# Main.net
KiCad netlist of a schematic drawn in Altium Designer
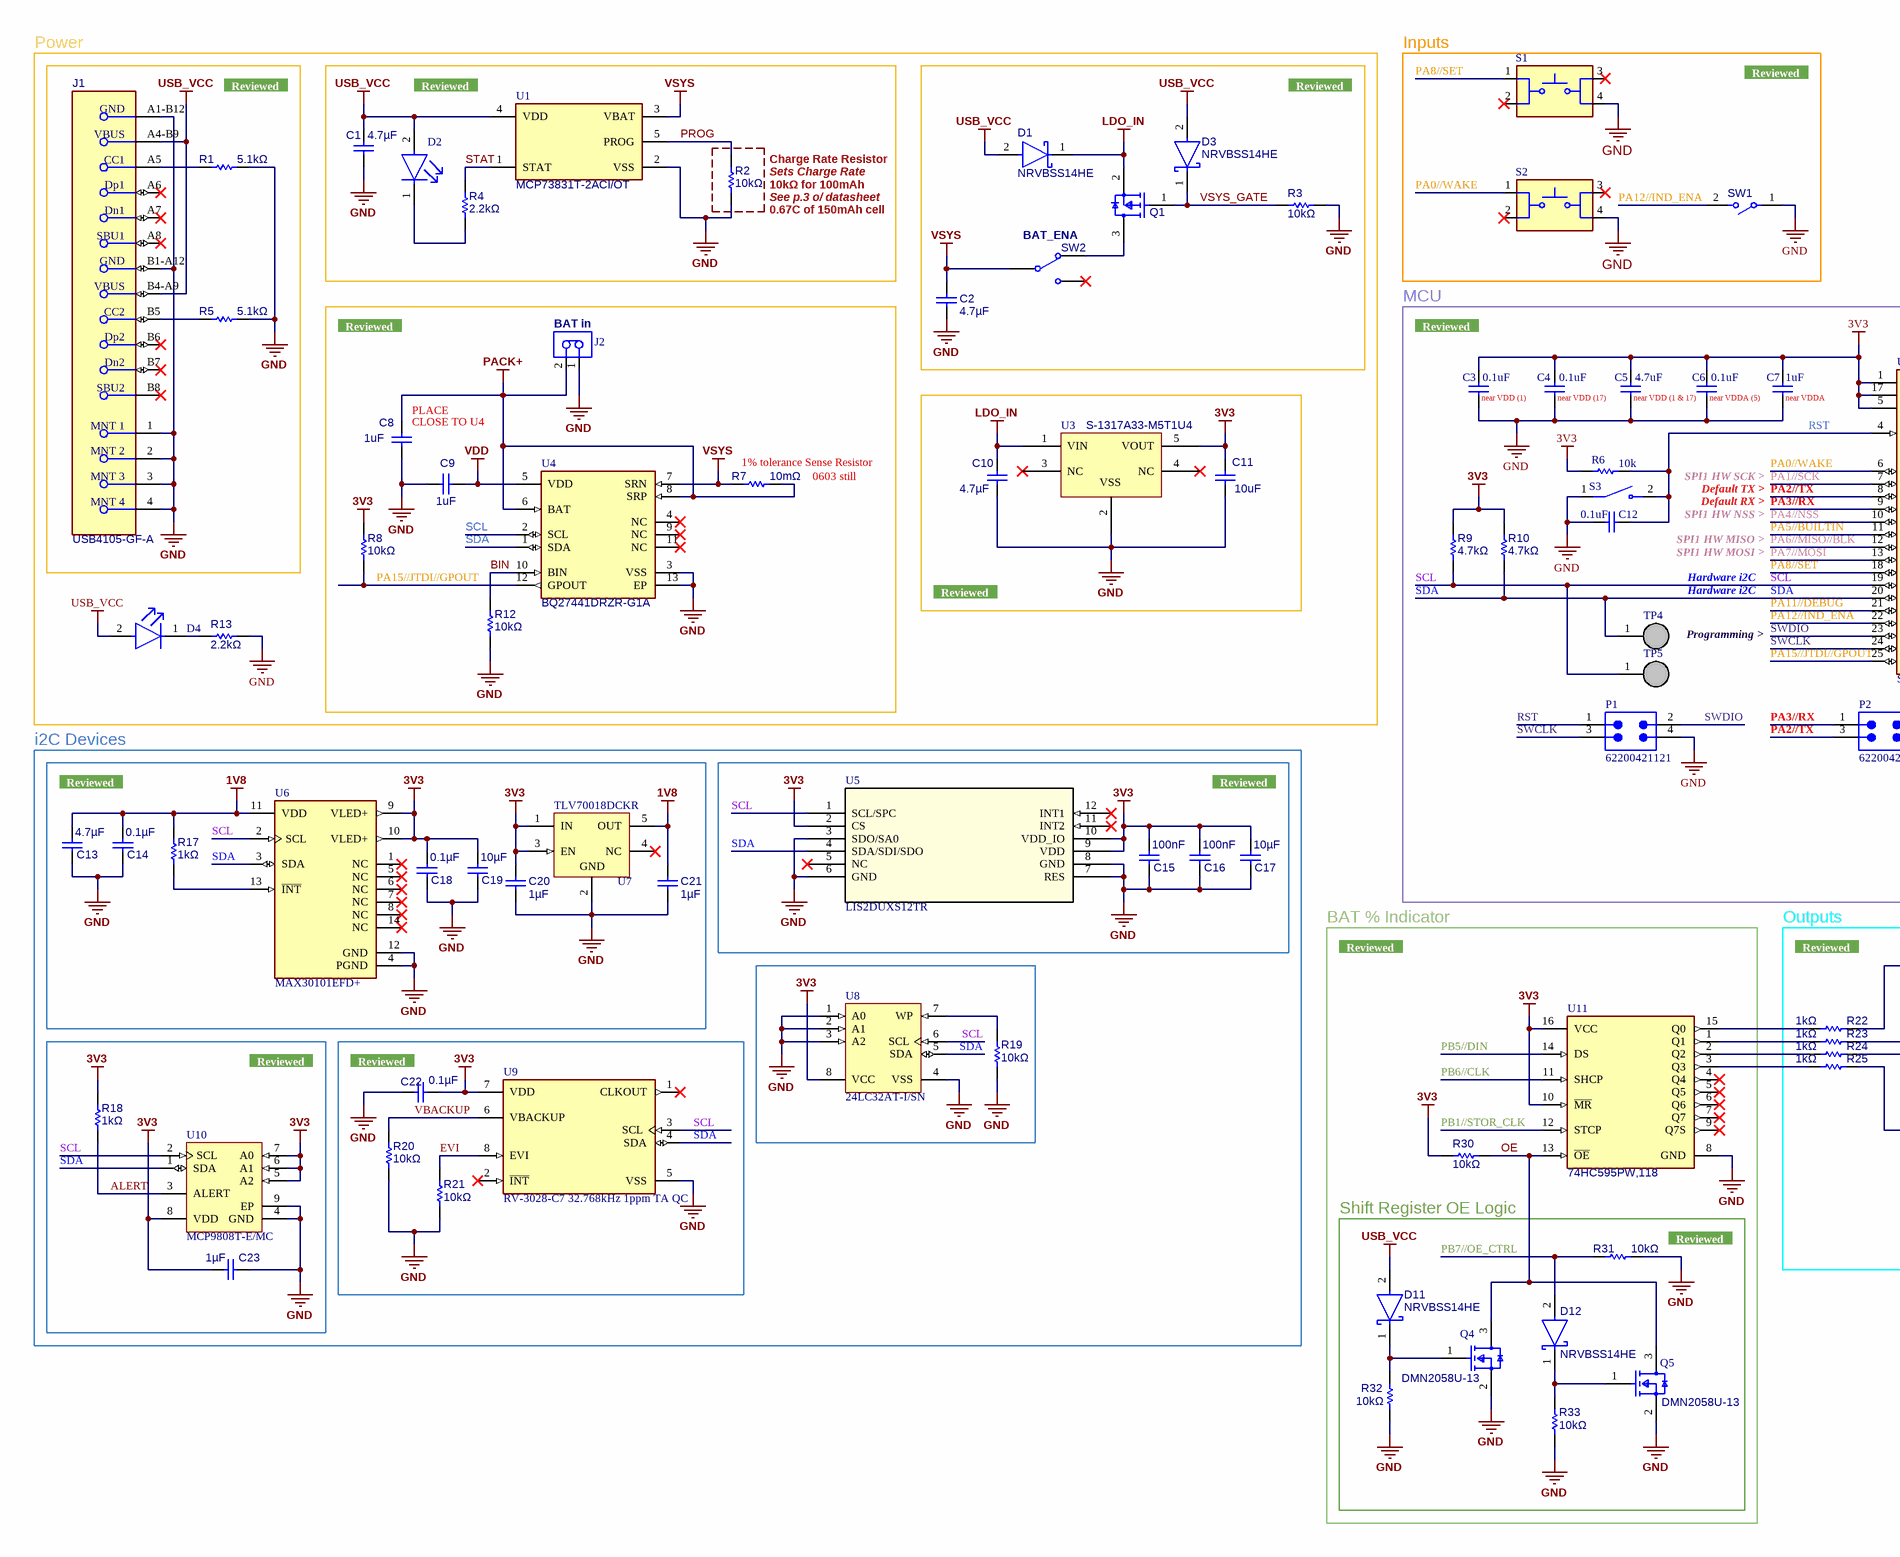
[diagram p0: Main.SchDoc, left]
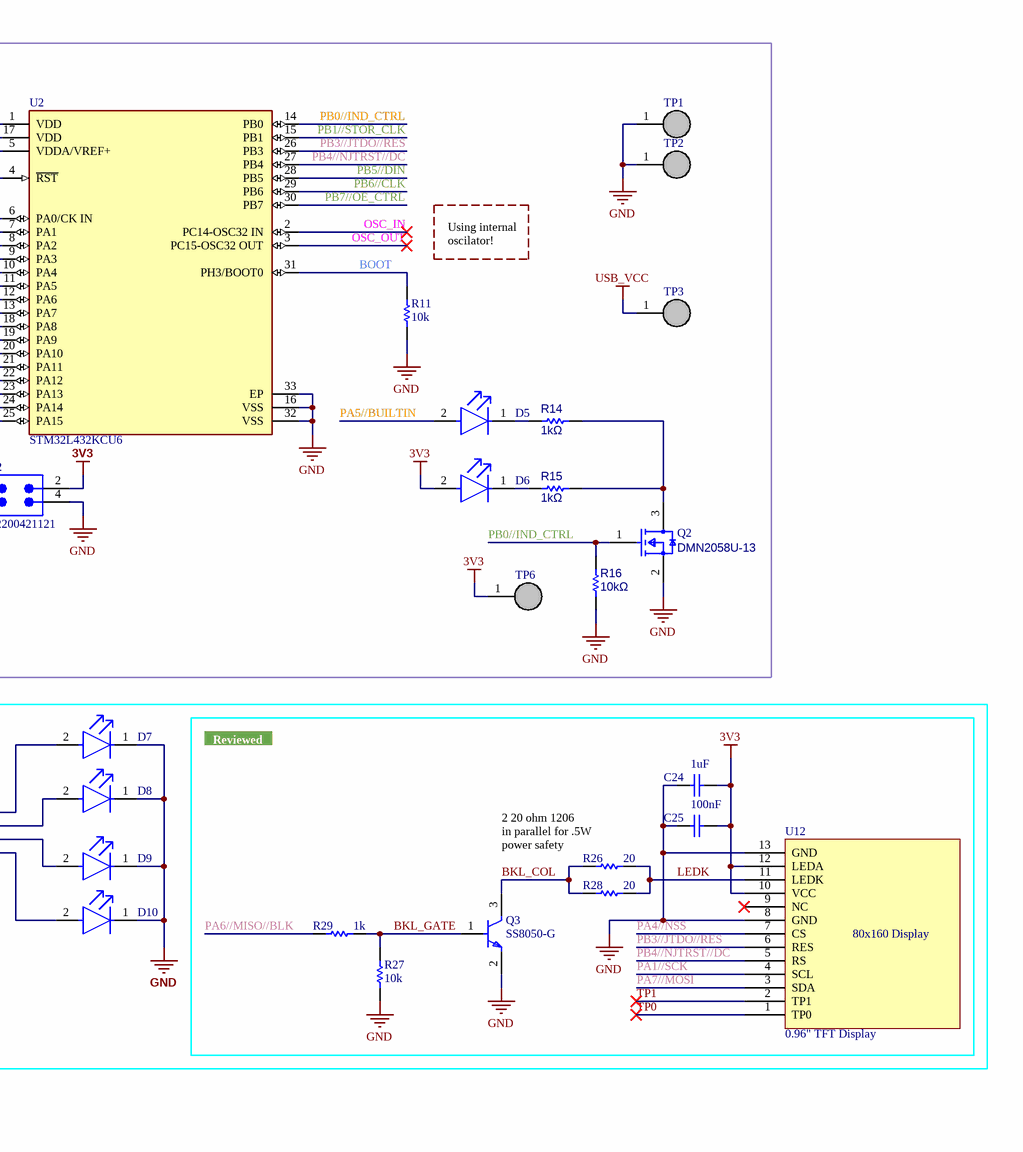
[diagram p1: Main.SchDoc, right]

(export (version "E")
  (design (tool "Eeschema 10.0.6"))
  (components
    (comp (ref "C1")
      (value "4.7µF")
      (footprint "WCAP-CSGP_0603_L1.6W0.8H0.8_Reflow")
      (libsource (lib "Altium Content Vault") (part "Capacitor_Non-Polarized"))
    )
    (comp (ref "C2")
      (value "4.7µF")
      (footprint "WCAP-CSGP_0603_L1.6W0.8H0.8_Reflow")
      (libsource (lib "Altium Content Vault") (part "Capacitor_Non-Polarized"))
    )
    (comp (ref "C3")
      (value "0.1uF")
      (footprint "CAPC1608X87X35NL15T15")
      (libsource (lib "Altium Content Vault") (part "CAP"))
    )
    (comp (ref "C4")
      (value "0.1uF")
      (footprint "CAPC1608X87X35NL15T15")
      (libsource (lib "Altium Content Vault") (part "CAP"))
    )
    (comp (ref "C5")
      (value "4.7uF")
      (footprint "CAPC1608X87X35NL15T15")
      (libsource (lib "Altium Content Vault") (part "CAP"))
    )
    (comp (ref "C6")
      (value "0.1uF")
      (footprint "CAPC1608X87X35NL15T15")
      (libsource (lib "Altium Content Vault") (part "CAP"))
    )
    (comp (ref "C7")
      (value "1uF")
      (footprint "CAPC1608X87X35NL15T15")
      (libsource (lib "Altium Content Vault") (part "CAP"))
    )
    (comp (ref "C8")
      (value "1uF")
      (footprint "WCAP-CSGP_0603_L1.6W0.8H0.8_Reflow")
      (libsource (lib "Altium Content Vault") (part "Capacitor_Non-Polarized"))
    )
    (comp (ref "C9")
      (value "1uF")
      (footprint "WCAP-CSGP_0603_L1.6W0.8H0.8_Reflow")
      (libsource (lib "Altium Content Vault") (part "Capacitor_Non-Polarized"))
    )
    (comp (ref "C10")
      (value "4.7µF")
      (footprint "WCAP-CSGP_0603_L1.6W0.8H0.8_Reflow")
      (libsource (lib "Altium Content Vault") (part "Capacitor_Non-Polarized"))
    )
    (comp (ref "C11")
      (value "10uF")
      (footprint "WCAP-CSGP_0603_L1.6W0.8H0.8_Reflow")
      (libsource (lib "Altium Content Vault") (part "Capacitor_Non-Polarized"))
    )
    (comp (ref "C12")
      (value "0.1uF")
      (footprint "CAPC1608X87X35NL15T15")
      (libsource (lib "Altium Content Vault") (part "CAP"))
    )
    (comp (ref "C13")
      (value "4.7µF")
      (footprint "WCAP-CSGP_0603_L1.6W0.8H0.8_Reflow")
      (description "10V tolerance")
      (libsource (lib "Altium Content Vault") (part "Capacitor_Non-Polarized"))
    )
    (comp (ref "C14")
      (value "0.1µF")
      (footprint "WCAP-CSGP_0603_L1.6W0.8H0.8_Reflow")
      (description "10V tolerance")
      (libsource (lib "Altium Content Vault") (part "Capacitor_Non-Polarized"))
    )
    (comp (ref "C15")
      (value "100nF")
      (footprint "WCAP-CSGP_0603_L1.6W0.8H0.8_Reflow")
      (description "10V tolerance")
      (libsource (lib "Altium Content Vault") (part "Capacitor_Non-Polarized"))
    )
    (comp (ref "C16")
      (value "100nF")
      (footprint "WCAP-CSGP_0603_L1.6W0.8H0.8_Reflow")
      (description "10V tolerance")
      (libsource (lib "Altium Content Vault") (part "Capacitor_Non-Polarized"))
    )
    (comp (ref "C17")
      (value "10µF")
      (footprint "WCAP-CSGP_0603_L1.6W0.8H0.8_Reflow")
      (description "10V tolerance")
      (libsource (lib "Altium Content Vault") (part "Capacitor_Non-Polarized"))
    )
    (comp (ref "C18")
      (value "0.1µF")
      (footprint "WCAP-CSGP_0603_L1.6W0.8H0.8_Reflow")
      (description "10V tolerance")
      (libsource (lib "Altium Content Vault") (part "Capacitor_Non-Polarized"))
    )
    (comp (ref "C19")
      (value "10µF")
      (footprint "WCAP-CSGP_0603_L1.6W0.8H0.8_Reflow")
      (description "10V tolerance")
      (libsource (lib "Altium Content Vault") (part "Capacitor_Non-Polarized"))
    )
    (comp (ref "C20")
      (value "1µF")
      (footprint "WCAP-CSGP_0603_L1.6W0.8H0.8_Reflow")
      (description "10V tolerance")
      (libsource (lib "Altium Content Vault") (part "Capacitor_Non-Polarized"))
    )
    (comp (ref "C21")
      (value "1µF")
      (footprint "WCAP-CSGP_0603_L1.6W0.8H0.8_Reflow")
      (description "10V tolerance")
      (libsource (lib "Altium Content Vault") (part "Capacitor_Non-Polarized"))
    )
    (comp (ref "C22")
      (value "0.1µF")
      (footprint "WCAP-CSGP_0603_L1.6W0.8H0.8_Reflow")
      (description "10V tolerance")
      (libsource (lib "Altium Content Vault") (part "Capacitor_Non-Polarized"))
    )
    (comp (ref "C23")
      (value "1µF")
      (footprint "WCAP-CSGP_0603_L1.6W0.8H0.8_Reflow")
      (description "10V tolerance")
      (libsource (lib "Altium Content Vault") (part "Capacitor_Non-Polarized"))
    )
    (comp (ref "C24")
      (value "1uF")
      (footprint "CAPC1608X87X35NL15T15")
      (libsource (lib "Altium Content Vault") (part "CAP"))
    )
    (comp (ref "C25")
      (value "100nF")
      (footprint "CAPC1608X87X35NL15T15")
      (libsource (lib "Altium Content Vault") (part "CAP"))
    )
    (comp (ref "D1")
      (value "NRVBSS14HE")
      (footprint "FP-477AD-MFG")
      (description "NRVBSS14HE Rectifier Diode, Schottky, 1 Phase, 1 Element, 1A, 40V V(RRM), Silicon")
      (libsource (lib "Altium Content Vault") (part "c1678fac7984e62e0809fbf79c06691"))
    )
    (comp (ref "D2")
      (value "LTST-C190KGKT")
      (footprint "FP-LTST-C190KGKT-MFG")
      (description "LED GREEN CLEAR CHIP SMD")
      (libsource (lib "Altium Content Vault") (part "8706943c75ba83719d021d2fdc84c58"))
    )
    (comp (ref "D3")
      (value "NRVBSS14HE")
      (footprint "FP-477AD-MFG")
      (description "NRVBSS14HE Rectifier Diode, Schottky, 1 Phase, 1 Element, 1A, 40V V(RRM), Silicon")
      (libsource (lib "Altium Content Vault") (part "c1678fac7984e62e0809fbf79c06691"))
    )
    (comp (ref "D4")
      (value "LTST-C190KGKT")
      (footprint "FP-LTST-C190KGKT-MFG")
      (description "LED GREEN CLEAR CHIP SMD")
      (libsource (lib "Altium Content Vault") (part "8706943c75ba83719d021d2fdc84c58"))
    )
    (comp (ref "D5")
      (value "LTST-C190KGKT")
      (footprint "FP-LTST-C190KGKT-MFG")
      (description "LED GREEN CLEAR CHIP SMD")
      (libsource (lib "Altium Content Vault") (part "8706943c75ba83719d021d2fdc84c58"))
    )
    (comp (ref "D6")
      (value "LTST-C190KGKT")
      (footprint "FP-LTST-C190KGKT-MFG")
      (description "LED GREEN CLEAR CHIP SMD")
      (libsource (lib "Altium Content Vault") (part "8706943c75ba83719d021d2fdc84c58"))
    )
    (comp (ref "D7")
      (value "LTST-C190KGKT")
      (footprint "FP-LTST-C190KGKT-MFG")
      (description "LED GREEN CLEAR CHIP SMD")
      (libsource (lib "Altium Content Vault") (part "8706943c75ba83719d021d2fdc84c58"))
    )
    (comp (ref "D8")
      (value "LTST-C190KGKT")
      (footprint "FP-LTST-C190KGKT-MFG")
      (description "LED GREEN CLEAR CHIP SMD")
      (libsource (lib "Altium Content Vault") (part "8706943c75ba83719d021d2fdc84c58"))
    )
    (comp (ref "D9")
      (value "LTST-C190KGKT")
      (footprint "FP-LTST-C190KGKT-MFG")
      (description "LED GREEN CLEAR CHIP SMD")
      (libsource (lib "Altium Content Vault") (part "8706943c75ba83719d021d2fdc84c58"))
    )
    (comp (ref "D10")
      (value "LTST-C190KGKT")
      (footprint "FP-LTST-C190KGKT-MFG")
      (description "LED GREEN CLEAR CHIP SMD")
      (libsource (lib "Altium Content Vault") (part "8706943c75ba83719d021d2fdc84c58"))
    )
    (comp (ref "D11")
      (value "NRVBSS14HE")
      (footprint "FP-477AD-MFG")
      (description "NRVBSS14HE Rectifier Diode, Schottky, 1 Phase, 1 Element, 1A, 40V V(RRM), Silicon")
      (libsource (lib "Altium Content Vault") (part "c1678fac7984e62e0809fbf79c06691"))
    )
    (comp (ref "D12")
      (value "NRVBSS14HE")
      (footprint "FP-477AD-MFG")
      (description "NRVBSS14HE Rectifier Diode, Schottky, 1 Phase, 1 Element, 1A, 40V V(RRM), Silicon")
      (libsource (lib "Altium Content Vault") (part "c1678fac7984e62e0809fbf79c06691"))
    )
    (comp (ref "J1")
      (value "USB4105-GF-A")
      (footprint "FP-USB4105-GF-A-MFG")
      (description "CONN RCPT USB2.0 TYPEC 5A")
      (fields
        (field (name "MANUFACTURER") "GCT")
        (field (name "OCTOPART") "https://octopart.com/usb4105-gf-a-gct-106627878")
      )
      (libsource (lib "Altium Content Vault") (part "e7c17a616881a82b79941196b4bec10"))
    )
    (comp (ref "J2")
      (value "B2B-PH-K-S(LF)(SN)")
      (footprint "JST-B2B-PH-K-S_V")
      (fields (field (name "MANUFACTURER") "JST"))
      (libsource (lib "Altium Content Vault") (part "CN-2P-F-QF2"))
    )
    (comp (ref "P1")
      (value "62200421121")
      (footprint "62200421121")
      (description "THT Vertical Pin Header WR-PHD, Pitch 1.27 mm, Dual Row, 4 pins")
      (libsource (lib "Altium Content Vault") (part "Header_Male_2R_04P"))
    )
    (comp (ref "P2")
      (value "62200421121")
      (footprint "62200421121")
      (description "THT Vertical Pin Header WR-PHD, Pitch 1.27 mm, Dual Row, 4 pins")
      (libsource (lib "Altium Content Vault") (part "Header_Male_2R_04P"))
    )
    (comp (ref "Q1")
      (value "IRLML6402TRPBF")
      (footprint "FP-Micro3-MFG")
      (description "MOSFET P-CH 20V 3.7A SOT-23")
      (fields
        (field (name "OCTOPART") "https://octopart.com/irlml6402trpbf-infineon-65874989")
        (field (name "MANUFACTURER") "Infineon")
      )
      (libsource (lib "Altium Content Vault") (part "566027c8dc92b5207d53ac25ab3eb60"))
    )
    (comp (ref "Q2")
      (value "DMN2058U-13")
      (footprint "FP-C04-17458-MFG")
      (description "TN2130K1-G Mosfet, N-Channel Enhancement-Mode, 300V, 25 Ohm Rohs Compliant: Yes")
      (libsource (lib "Altium Content Vault") (part "3b9c635fedb024a5347a57b145af9cc"))
    )
    (comp (ref "Q3")
      (value "SS8050-G")
      (footprint "FP-SS8050-G-MFG")
      (description "NPN TRANSISTOR 1.5A 40V SOT-23 R")
      (libsource (lib "Altium Content Vault") (part "2a1388f82443b098dcd57d24ac7632d"))
    )
    (comp (ref "Q4")
      (value "DMN2058U-13")
      (footprint "FP-C04-17458-MFG")
      (description "TN2130K1-G Mosfet, N-Channel Enhancement-Mode, 300V, 25 Ohm Rohs Compliant: Yes")
      (libsource (lib "Altium Content Vault") (part "3b9c635fedb024a5347a57b145af9cc"))
    )
    (comp (ref "Q5")
      (value "DMN2058U-13")
      (footprint "FP-C04-17458-MFG")
      (description "TN2130K1-G Mosfet, N-Channel Enhancement-Mode, 300V, 25 Ohm Rohs Compliant: Yes")
      (libsource (lib "Altium Content Vault") (part "3b9c635fedb024a5347a57b145af9cc"))
    )
    (comp (ref "R1")
      (value "5.1kΩ")
      (footprint "RESC1608X55X25NL10T15")
      (libsource (lib "Altium Content Vault") (part "RES"))
    )
    (comp (ref "R2")
      (value "10kΩ")
      (footprint "RESC1608X55X25NL10T15")
      (libsource (lib "Altium Content Vault") (part "RES"))
    )
    (comp (ref "R3")
      (value "10kΩ")
      (footprint "RESC1608X55X25NL10T15")
      (libsource (lib "Altium Content Vault") (part "RES"))
    )
    (comp (ref "R4")
      (value "2.2kΩ")
      (footprint "RESC1608X55X25NL10T15")
      (libsource (lib "Altium Content Vault") (part "RES"))
    )
    (comp (ref "R5")
      (value "5.1kΩ")
      (footprint "RESC1608X55X25NL10T15")
      (libsource (lib "Altium Content Vault") (part "RES"))
    )
    (comp (ref "R6")
      (value "10k")
      (footprint "RESC1608X55X25NL10T15")
      (fields (field (name "PART NUMBER") "RT0603BRE071KL") (field (name "MANUFACTURER") "Yageo"))
      (libsource (lib "Altium Content Vault") (part "RES"))
    )
    (comp (ref "R7")
      (value "10mΩ")
      (footprint "RESC1608X55X25NL10T15")
      (libsource (lib "Altium Content Vault") (part "RES"))
    )
    (comp (ref "R8")
      (value "10kΩ")
      (footprint "RESC1608X55X25NL10T15")
      (libsource (lib "Altium Content Vault") (part "RES"))
    )
    (comp (ref "R9")
      (value "4.7kΩ")
      (footprint "RESC1608X55X25NL10T15")
      (libsource (lib "Altium Content Vault") (part "RES"))
    )
    (comp (ref "R10")
      (value "4.7kΩ")
      (footprint "RESC1608X55X25NL10T15")
      (libsource (lib "Altium Content Vault") (part "RES"))
    )
    (comp (ref "R11")
      (value "10k")
      (footprint "RESC1608X55X25NL10T15")
      (fields (field (name "PART NUMBER") "RT0603BRE071KL") (field (name "MANUFACTURER") "Yageo"))
      (libsource (lib "Altium Content Vault") (part "RES"))
    )
    (comp (ref "R12")
      (value "10kΩ")
      (footprint "RESC1608X55X25NL10T15")
      (libsource (lib "Altium Content Vault") (part "RES"))
    )
    (comp (ref "R13")
      (value "2.2kΩ")
      (footprint "RESC1608X55X25NL10T15")
      (libsource (lib "Altium Content Vault") (part "RES"))
    )
    (comp (ref "R14")
      (value "1kΩ")
      (footprint "RESC1608X55X25NL10T15")
      (libsource (lib "Altium Content Vault") (part "RES"))
    )
    (comp (ref "R15")
      (value "1kΩ")
      (footprint "RESC1608X55X25NL10T15")
      (libsource (lib "Altium Content Vault") (part "RES"))
    )
    (comp (ref "R16")
      (value "10kΩ")
      (footprint "RESC1608X55X25NL10T15")
      (libsource (lib "Altium Content Vault") (part "RES"))
    )
    (comp (ref "R17")
      (value "1kΩ")
      (footprint "RESC1608X55X25NL10T15")
      (libsource (lib "Altium Content Vault") (part "RES"))
    )
    (comp (ref "R18")
      (value "1kΩ")
      (footprint "RESC1608X55X25NL10T15")
      (libsource (lib "Altium Content Vault") (part "RES"))
    )
    (comp (ref "R19")
      (value "10kΩ")
      (footprint "RESC1608X55X25NL10T15")
      (libsource (lib "Altium Content Vault") (part "RES"))
    )
    (comp (ref "R20")
      (value "10kΩ")
      (footprint "RESC1608X55X25NL10T15")
      (libsource (lib "Altium Content Vault") (part "RES"))
    )
    (comp (ref "R21")
      (value "10kΩ")
      (footprint "RESC1608X55X25NL10T15")
      (libsource (lib "Altium Content Vault") (part "RES"))
    )
    (comp (ref "R22")
      (value "1kΩ")
      (footprint "RESC1608X55X25NL10T15")
      (libsource (lib "Altium Content Vault") (part "RES"))
    )
    (comp (ref "R23")
      (value "1kΩ")
      (footprint "RESC1608X55X25NL10T15")
      (libsource (lib "Altium Content Vault") (part "RES"))
    )
    (comp (ref "R24")
      (value "1kΩ")
      (footprint "RESC1608X55X25NL10T15")
      (libsource (lib "Altium Content Vault") (part "RES"))
    )
    (comp (ref "R25")
      (value "1kΩ")
      (footprint "RESC1608X55X25NL10T15")
      (libsource (lib "Altium Content Vault") (part "RES"))
    )
    (comp (ref "R26")
      (value "20")
      (footprint "RESC3116X65X40NL10T20")
      (fields (field (name "MANUFACTURER") "Yageo") (field (name "PART NUMBER") "RC1206JR-0720RL"))
      (libsource (lib "Altium Content Vault") (part "RES"))
    )
    (comp (ref "R27")
      (value "10k")
      (footprint "RESC1608X55X25NL10T15")
      (fields (field (name "PART NUMBER") "RT0603BRE071KL") (field (name "MANUFACTURER") "Yageo"))
      (libsource (lib "Altium Content Vault") (part "RES"))
    )
    (comp (ref "R28")
      (value "20")
      (footprint "RESC3116X65X40NL10T20")
      (fields (field (name "MANUFACTURER") "Yageo") (field (name "PART NUMBER") "RC1206JR-0720RL"))
      (libsource (lib "Altium Content Vault") (part "RES"))
    )
    (comp (ref "R29")
      (value "1k")
      (footprint "RESC1608X55X25NL10T15")
      (fields (field (name "PART NUMBER") "RT0603BRE071KL") (field (name "MANUFACTURER") "Yageo"))
      (libsource (lib "Altium Content Vault") (part "RES"))
    )
    (comp (ref "R30")
      (value "10kΩ")
      (footprint "RESC1608X55X25NL10T15")
      (libsource (lib "Altium Content Vault") (part "RES"))
    )
    (comp (ref "R31")
      (value "10kΩ")
      (footprint "RESC1608X55X25NL10T15")
      (libsource (lib "Altium Content Vault") (part "RES"))
    )
    (comp (ref "R32")
      (value "10kΩ")
      (footprint "RESC1608X55X25NL10T15")
      (libsource (lib "Altium Content Vault") (part "RES"))
    )
    (comp (ref "R33")
      (value "10kΩ")
      (footprint "RESC1608X55X25NL10T15")
      (libsource (lib "Altium Content Vault") (part "RES"))
    )
    (comp (ref "S1")
      (value "SWT0325-073016TSK_REVA")
      (footprint "SW_SWT0325-073016TSK_REVA")
      (description "6mm x 6mm Through Hole Tactile Switch")
      (fields (field (name "MF") "Global Connector Technology") (field (name "MP") "SWT0325-073016TSK"))
      (libsource (lib "SWT0325-073016TSK_REVA") (part "SWT0325-073016TSK_REVA"))
    )
    (comp (ref "S2")
      (value "SWT0325-073016TSK_REVA")
      (footprint "SW_SWT0325-073016TSK_REVA")
      (description "6mm x 6mm Through Hole Tactile Switch")
      (fields (field (name "MF") "Global Connector Technology") (field (name "MP") "SWT0325-073016TSK"))
      (libsource (lib "SWT0325-073016TSK_REVA") (part "SWT0325-073016TSK_REVA"))
    )
    (comp (ref "S3")
      (value "TS09-63-25-WT-260-SMT-TR")
      (footprint "SW_TS09-63-25-WT-260-SMT-TR")
      (description "6.1 x 3.7 mm, 2.5 mm Actuator Height, 260 gf, White, Surface Mount, SPST, Tactile Switch")
      (fields (field (name "MF") "Same Sky"))
      (libsource (lib "TS09-63-25-WT-260-SMT-TR") (part "TS09-63-25-WT-260-SMT-TR"))
    )
    (comp (ref "SW1")
      (value "B3U-1000P-B")
      (footprint "FP-B3U-1000P-B-MFG")
      (description "SWITCH TACTILE SPST-NO 0.05A 12V")
      (fields
        (field (name "OCTOPART") "https://octopart.com/b3u-1000p-b-omron-1057356")
        (field (name "MANUFACTURER") "Omron")
      )
      (libsource (lib "Altium Content Vault") (part "bb27bde45df87f1f469753f287ef5ae"))
    )
    (comp (ref "SW2")
      (value "450404015514")
      (footprint "450404015514")
      (description "450404015514 Slide Switch, 0.3A, 5Vdc, Smd Rohs Compliant: Yes")
      (libsource (lib "Altium Content Vault") (part "SPDT"))
    )
    (comp (ref "TP1")
      (value "Testpoint")
      (footprint "Testpoint Footprint")
      (libsource (lib "DebuggingLib") (part "Testpoint"))
    )
    (comp (ref "TP2")
      (value "Testpoint")
      (footprint "Testpoint Footprint")
      (libsource (lib "DebuggingLib") (part "Testpoint"))
    )
    (comp (ref "TP3")
      (value "Testpoint")
      (footprint "Testpoint Footprint")
      (libsource (lib "DebuggingLib") (part "Testpoint"))
    )
    (comp (ref "TP4")
      (value "Testpoint")
      (footprint "Testpoint Footprint")
      (libsource (lib "DebuggingLib") (part "Testpoint"))
    )
    (comp (ref "TP5")
      (value "Testpoint")
      (footprint "Testpoint Footprint")
      (libsource (lib "DebuggingLib") (part "Testpoint"))
    )
    (comp (ref "TP6")
      (value "Testpoint")
      (footprint "Testpoint Footprint")
      (libsource (lib "DebuggingLib") (part "Testpoint"))
    )
    (comp (ref "U1")
      (value "MCP73831T-2ACI/OT")
      (footprint "FP-C04-091-OT-MFG")
      (description "IC CONTROLLR LI-ION 4.2V SOT23-5")
      (libsource (lib "Altium Content Vault") (part "61f5a3bb3429d9e0caadea342aa3b19"))
    )
    (comp (ref "U2")
      (value "STM32L432KCU6")
      (footprint "FP-UFQFPN32-A0B8-MFG")
      (description "IC MCU 32BIT 256KB FLASH 32QFPN")
      (fields
        (field (name "OCTOPART") "https://octopart.com/stm32l432kcu6-stmicroelectronics-71093510")
        (field (name "MANUFACTURER") "STMicroelectronics")
      )
      (libsource (lib "Altium Content Vault") (part "f3240dca552e0aa49c1b4baba198c12"))
    )
    (comp (ref "U3")
      (value "S-1317A33-M5T1U4")
      (footprint "S-1317A33-M5T1U4")
      (libsource (lib "1317A33-M5T1U4") (part "S-1317A33-M5T1U4"))
    )
    (comp (ref "U4")
      (value "BQ27441DRZR-G1A")
      (footprint "FP-DRZ0012A-MFG")
      (description "IC BATT FUEL GAUGE LI-ION 12SON")
      (fields
        (field (name "OCTOPART") "https://octopart.com/bq27441drzr-g1a-texas+instruments-30555829")
        (field (name "MANUFACTURER") "Texas Instruments")
      )
      (libsource (lib "Altium Content Vault") (part "0f562f18464a1f07b55dcd927f1fdf2"))
    )
    (comp (ref "U5")
      (value "LIS2DUXS12TR")
      (footprint "QFN_DUXS12_STM")
      (fields (field (name "COPYRIGHT") "Copyright (C) 2025 Ultra Librarian. All rights reserved."))
      (libsource (lib "LIS2DUXS12TR") (part "LIS2DUXS12TR"))
    )
    (comp (ref "U6")
      (value "MAX30101EFD+")
      (footprint "FP-F143A5-1-MFG")
      (description "INTEGRATED OPTICAL SENSOR")
      (fields
        (field (name "MANUFACTURER") "Maxim Integrated")
        (field (name "OCTOPART") "https://octopart.com/max30101efd%2B-maxim+integrated-57054333")
      )
      (libsource (lib "Altium Content Vault") (part "7412f82398c18c21c59cad441ae59a4"))
    )
    (comp (ref "U7")
      (value "TLV70018DCKR")
      (footprint "DCK0005A_L")
      (fields (field (name "MANUFACTURER") "Texas Instruments"))
      (libsource (lib "Altium Content Vault") (part "TI-TXX7XXXX-5"))
    )
    (comp (ref "U8")
      (value "24LC32AT-I/SN")
      (footprint "SOIC-SN8_L")
      (description "32Kbit, 400kHz, 2.5V, I2C Serial EEPROM, 8-Pin SOIC 150mil, Industrial Temperature, Tape and Reel")
      (libsource (lib "Altium Content Vault") (part "MEM-SEEPROM-34AA02-IL8"))
    )
    (comp (ref "U9")
      (value "RV-3028-C7 32.768kHz 1ppm TA QC")
      (footprint "FP-RV-3028-C7_32_768kHz_1-MFG")
      (description "Real Time Clock Serial 2byte Clock/Calendar/Alarm/Timer/Battery Backup 8-Pin CSMD T/R")
      (fields
        (field (name "OCTOPART") "https://octopart.com/rv-3028-c7+32.768khz+1ppm+ta+qc-micro+crystal-98880451")
        (field (name "MANUFACTURER") "Micro Crystal")
      )
      (libsource (lib "Altium Content Vault") (part "f06799675b941e5ee1fb77ef065374c"))
    )
    (comp (ref "U10")
      (value "MCP9808T-E/MC")
      (footprint "MCHP-DFN-MC8_V")
      (fields (field (name "MANUFACTURER") "Microchip"))
      (libsource (lib "Altium Content Vault") (part "MCHP-MCP9808-DFN-8"))
    )
    (comp (ref "U11")
      (value "74HC595PW,118")
      (footprint "FP-SOT403-1-MFG")
      (description "IC SHIFT REGISTER 8BIT 16TSSOP")
      (libsource (lib "Altium Content Vault") (part "27683e23285b137cd268a0f18c66bed"))
    )
    (comp (ref "U12")
      (value "0.96\" TFT Display")
      (footprint "PCBComponent_1")
      (libsource (lib "disp_0.96") (part "0.96{dblquote} TFT Display"))
    )
  )
  (nets
    (net (code "1") (name "/ALERT") (class "Default")
      (node (ref "R18") (pin "1") (pinfunction "1_1") (pintype "passive"))
      (node (ref "U10") (pin "3") (pinfunction "ALERT_3") (pintype "open_collector"))
    )
    (net (code "2") (name "/BIN") (class "Default")
      (node (ref "R12") (pin "2") (pinfunction "2_2") (pintype "passive"))
      (node (ref "U4") (pin "10") (pinfunction "BIN_10") (pintype "input"))
    )
    (net (code "3") (name "/BKL_COL") (class "Default")
      (node (ref "Q3") (pin "3") (pinfunction "C_3") (pintype "passive"))
      (node (ref "R26") (pin "1") (pinfunction "1_1") (pintype "passive"))
      (node (ref "R28") (pin "1") (pinfunction "1_1") (pintype "passive"))
    )
    (net (code "4") (name "/BKL_GATE") (class "Default")
      (node (ref "Q3") (pin "1") (pinfunction "B_1") (pintype "passive"))
      (node (ref "R27") (pin "2") (pinfunction "2_2") (pintype "passive"))
      (node (ref "R29") (pin "2") (pinfunction "2_2") (pintype "passive"))
    )
    (net (code "5") (name "/BOOT") (class "Default")
      (node (ref "R11") (pin "2") (pinfunction "2_2") (pintype "passive"))
      (node (ref "U2") (pin "31") (pinfunction "PH3/BOOT0_31") (pintype "bidirectional"))
    )
    (net (code "6") (name "/EVI") (class "Default")
      (node (ref "R21") (pin "2") (pinfunction "2_2") (pintype "passive"))
      (node (ref "U9") (pin "8") (pinfunction "EVI_8") (pintype "input"))
    )
    (net (code "7") (name "/LEDK") (class "Default")
      (node (ref "R26") (pin "2") (pinfunction "2_2") (pintype "passive"))
      (node (ref "R28") (pin "2") (pinfunction "2_2") (pintype "passive"))
      (node (ref "U12") (pin "11") (pinfunction "LEDK_11") (pintype "passive"))
    )
    (net (code "8") (name "/OE") (class "Default")
      (node (ref "Q4") (pin "3") (pinfunction "D_3") (pintype "passive"))
      (node (ref "Q5") (pin "3") (pinfunction "D_3") (pintype "passive"))
      (node (ref "R30") (pin "2") (pinfunction "2_2") (pintype "passive"))
      (node (ref "U11") (pin "13") (pinfunction "~{OE}_13") (pintype "input"))
    )
    (net (code "9") (name "/OSC_IN") (class "Default")
      (node (ref "U2") (pin "2") (pinfunction "PC14-OSC32_IN_2") (pintype "bidirectional+no_connect"))
    )
    (net (code "10") (name "/OSC_OUT") (class "Default")
      (node (ref "U2") (pin "3") (pinfunction "PC15-OSC32_OUT_3") (pintype "bidirectional+no_connect"))
    )
    (net (code "11") (name "/PA0{slash}{slash}WAKE") (class "Default")
      (node (ref "S2") (pin "1") (pinfunction "1_1") (pintype "passive"))
      (node (ref "U2") (pin "6") (pinfunction "PA0/CK_IN_6") (pintype "bidirectional"))
    )
    (net (code "12") (name "/PA1{slash}{slash}SCK") (class "Default")
      (node (ref "U12") (pin "4") (pinfunction "SCL_4") (pintype "passive"))
      (node (ref "U2") (pin "7") (pinfunction "PA1_7") (pintype "bidirectional"))
    )
    (net (code "13") (name "/PA2{slash}{slash}TX") (class "Default")
      (node (ref "P2") (pin "3") (pinfunction "3_3") (pintype "passive"))
      (node (ref "U2") (pin "8") (pinfunction "PA2_8") (pintype "bidirectional"))
    )
    (net (code "14") (name "/PA3{slash}{slash}RX") (class "Default")
      (node (ref "P2") (pin "1") (pinfunction "1_1") (pintype "passive"))
      (node (ref "U2") (pin "9") (pinfunction "PA3_9") (pintype "bidirectional"))
    )
    (net (code "15") (name "/PA4{slash}{slash}NSS") (class "Default")
      (node (ref "U12") (pin "7") (pinfunction "CS_7") (pintype "passive"))
      (node (ref "U2") (pin "10") (pinfunction "PA4_10") (pintype "bidirectional"))
    )
    (net (code "16") (name "/PA5{slash}{slash}BUILTIN") (class "Default")
      (node (ref "D5") (pin "2") (pinfunction "A_2") (pintype "passive"))
      (node (ref "U2") (pin "11") (pinfunction "PA5_11") (pintype "bidirectional"))
    )
    (net (code "17") (name "/PA6{slash}{slash}MISO{slash}{slash}BLK") (class "Default")
      (node (ref "R29") (pin "1") (pinfunction "1_1") (pintype "passive"))
      (node (ref "U2") (pin "12") (pinfunction "PA6_12") (pintype "bidirectional"))
    )
    (net (code "18") (name "/PA7{slash}{slash}MOSI") (class "Default")
      (node (ref "U12") (pin "3") (pinfunction "SDA_3") (pintype "passive"))
      (node (ref "U2") (pin "13") (pinfunction "PA7_13") (pintype "bidirectional"))
    )
    (net (code "19") (name "/PA8{slash}{slash}SET") (class "Default")
      (node (ref "S1") (pin "1") (pinfunction "1_1") (pintype "passive"))
      (node (ref "U2") (pin "18") (pinfunction "PA8_18") (pintype "bidirectional"))
    )
    (net (code "20") (name "/PA11{slash}{slash}DEBUG") (class "Default")
      (node (ref "U2") (pin "21") (pinfunction "PA11_21") (pintype "bidirectional"))
    )
    (net (code "21") (name "/PA12{slash}{slash}IND_ENA") (class "Default")
      (node (ref "SW1") (pin "2") (pinfunction "2_2") (pintype "passive"))
      (node (ref "U2") (pin "22") (pinfunction "PA12_22") (pintype "bidirectional"))
    )
    (net (code "22") (name "/PA15{slash}{slash}JTDI{slash}{slash}GPOUT") (class "Default")
      (node (ref "R8") (pin "1") (pinfunction "1_1") (pintype "passive"))
      (node (ref "U2") (pin "25") (pinfunction "PA15_25") (pintype "bidirectional"))
      (node (ref "U4") (pin "12") (pinfunction "GPOUT_12") (pintype "output"))
    )
    (net (code "23") (name "/PB0{slash}{slash}IND_CTRL") (class "Default")
      (node (ref "Q2") (pin "1") (pinfunction "G_1") (pintype "passive"))
      (node (ref "R16") (pin "2") (pinfunction "2_2") (pintype "passive"))
      (node (ref "U2") (pin "14") (pinfunction "PB0_14") (pintype "bidirectional"))
    )
    (net (code "24") (name "/PB1{slash}{slash}STOR_CLK") (class "Default")
      (node (ref "U11") (pin "12") (pinfunction "STCP_12") (pintype "input"))
      (node (ref "U2") (pin "15") (pinfunction "PB1_15") (pintype "bidirectional"))
    )
    (net (code "25") (name "/PB3{slash}{slash}JTDO{slash}{slash}RES") (class "Default")
      (node (ref "U12") (pin "6") (pinfunction "RES_6") (pintype "passive"))
      (node (ref "U2") (pin "26") (pinfunction "PB3_26") (pintype "bidirectional"))
    )
    (net (code "26") (name "/PB4{slash}{slash}NJTRST{slash}{slash}DC") (class "Default")
      (node (ref "U12") (pin "5") (pinfunction "RS_5") (pintype "passive"))
      (node (ref "U2") (pin "27") (pinfunction "PB4_27") (pintype "bidirectional"))
    )
    (net (code "27") (name "/PB5{slash}{slash}DIN") (class "Default")
      (node (ref "U11") (pin "14") (pinfunction "DS_14") (pintype "input"))
      (node (ref "U2") (pin "28") (pinfunction "PB5_28") (pintype "bidirectional"))
    )
    (net (code "28") (name "/PB6{slash}{slash}CLK") (class "Default")
      (node (ref "U11") (pin "11") (pinfunction "SHCP_11") (pintype "input"))
      (node (ref "U2") (pin "29") (pinfunction "PB6_29") (pintype "bidirectional"))
    )
    (net (code "29") (name "/PB7{slash}{slash}OE_CTRL") (class "Default")
      (node (ref "D12") (pin "2") (pinfunction "A_2") (pintype "passive"))
      (node (ref "R31") (pin "1") (pinfunction "1_1") (pintype "passive"))
      (node (ref "U2") (pin "30") (pinfunction "PB7_30") (pintype "bidirectional"))
    )
    (net (code "30") (name "/PROG") (class "Default")
      (node (ref "R2") (pin "1") (pinfunction "1_1") (pintype "passive"))
      (node (ref "U1") (pin "5") (pinfunction "PROG_5") (pintype "passive"))
    )
    (net (code "31") (name "/RST") (class "Default")
      (node (ref "C12") (pin "2") (pinfunction "2_2") (pintype "passive"))
      (node (ref "P1") (pin "1") (pinfunction "1_1") (pintype "passive"))
      (node (ref "R6") (pin "1") (pinfunction "1_1") (pintype "passive"))
      (node (ref "S3") (pin "2") (pinfunction "2_2") (pintype "passive"))
      (node (ref "U2") (pin "4") (pinfunction "~{RST}_4") (pintype "input"))
    )
    (net (code "32") (name "/SCL") (class "Default")
      (node (ref "R9") (pin "2") (pinfunction "2_2") (pintype "passive"))
      (node (ref "TP5") (pin "1") (pintype "passive"))
      (node (ref "U10") (pin "2") (pinfunction "SCL_2") (pintype "input"))
      (node (ref "U2") (pin "19") (pinfunction "PA9_19") (pintype "bidirectional"))
      (node (ref "U4") (pin "2") (pinfunction "SCL_2") (pintype "bidirectional"))
      (node (ref "U5") (pin "1") (pinfunction "SCL/SPC_1") (pintype "passive"))
      (node (ref "U6") (pin "2") (pinfunction "SCL_2") (pintype "input"))
      (node (ref "U8") (pin "6") (pinfunction "SCL_6") (pintype "input"))
      (node (ref "U9") (pin "3") (pinfunction "SCL_3") (pintype "input"))
    )
    (net (code "33") (name "/SDA") (class "Default")
      (node (ref "R10") (pin "2") (pinfunction "2_2") (pintype "passive"))
      (node (ref "TP4") (pin "1") (pintype "passive"))
      (node (ref "U10") (pin "1") (pinfunction "SDA_1") (pintype "bidirectional"))
      (node (ref "U2") (pin "20") (pinfunction "PA10_20") (pintype "bidirectional"))
      (node (ref "U4") (pin "1") (pinfunction "SDA_1") (pintype "bidirectional"))
      (node (ref "U5") (pin "4") (pinfunction "SDA/SDI/SDO_4") (pintype "passive"))
      (node (ref "U6") (pin "3") (pinfunction "SDA_3") (pintype "bidirectional"))
      (node (ref "U8") (pin "5") (pinfunction "SDA_5") (pintype "bidirectional"))
      (node (ref "U9") (pin "4") (pinfunction "SDA_4") (pintype "bidirectional"))
    )
    (net (code "34") (name "/STAT") (class "Default")
      (node (ref "R4") (pin "2") (pinfunction "2_2") (pintype "passive"))
      (node (ref "U1") (pin "1") (pinfunction "STAT_1") (pintype "passive"))
    )
    (net (code "35") (name "/SWCLK") (class "Default")
      (node (ref "P1") (pin "3") (pinfunction "3_3") (pintype "passive"))
      (node (ref "U2") (pin "24") (pinfunction "PA14_24") (pintype "bidirectional"))
    )
    (net (code "36") (name "/SWDIO") (class "Default")
      (node (ref "P1") (pin "2") (pinfunction "2_2") (pintype "passive"))
      (node (ref "U2") (pin "23") (pinfunction "PA13_23") (pintype "bidirectional"))
    )
    (net (code "37") (name "/TP0") (class "Default")
      (node (ref "U12") (pin "1") (pinfunction "TP0_1") (pintype "passive+no_connect"))
    )
    (net (code "38") (name "/TP1") (class "Default")
      (node (ref "U12") (pin "2") (pinfunction "TP1_2") (pintype "passive+no_connect"))
    )
    (net (code "39") (name "/VBACKUP") (class "Default")
      (node (ref "R20") (pin "2") (pinfunction "2_2") (pintype "passive"))
      (node (ref "U9") (pin "6") (pinfunction "VBACKUP_6") (pintype "power_in"))
    )
    (net (code "40") (name "/VSYS_GATE") (class "Default")
      (node (ref "D3") (pin "1") (pinfunction "C_1") (pintype "passive"))
      (node (ref "Q1") (pin "1") (pinfunction "G_1") (pintype "passive"))
      (node (ref "R3") (pin "1") (pinfunction "1_1") (pintype "passive"))
    )
    (net (code "41") (name "1V8") (class "Default")
      (node (ref "C13") (pin "1") (pinfunction "1_1") (pintype "passive"))
      (node (ref "C14") (pin "1") (pinfunction "1_1") (pintype "passive"))
      (node (ref "C21") (pin "2") (pinfunction "2_2") (pintype "passive"))
      (node (ref "R17") (pin "2") (pinfunction "2_2") (pintype "passive"))
      (node (ref "U6") (pin "11") (pinfunction "VDD_11") (pintype "power_in"))
      (node (ref "U7") (pin "5") (pinfunction "OUT_5") (pintype "power_in"))
    )
    (net (code "42") (name "3V3") (class "Default")
      (node (ref "C11") (pin "2") (pinfunction "2_2") (pintype "passive"))
      (node (ref "C15") (pin "1") (pinfunction "1_1") (pintype "passive"))
      (node (ref "C16") (pin "1") (pinfunction "1_1") (pintype "passive"))
      (node (ref "C17") (pin "1") (pinfunction "1_1") (pintype "passive"))
      (node (ref "C18") (pin "1") (pinfunction "1_1") (pintype "passive"))
      (node (ref "C19") (pin "1") (pinfunction "1_1") (pintype "passive"))
      (node (ref "C20") (pin "2") (pinfunction "2_2") (pintype "passive"))
      (node (ref "C22") (pin "1") (pinfunction "1_1") (pintype "passive"))
      (node (ref "C23") (pin "1") (pinfunction "1_1") (pintype "passive"))
      (node (ref "C24") (pin "1") (pinfunction "1_1") (pintype "passive"))
      (node (ref "C25") (pin "1") (pinfunction "1_1") (pintype "passive"))
      (node (ref "C3") (pin "1") (pinfunction "1_1") (pintype "passive"))
      (node (ref "C4") (pin "1") (pinfunction "1_1") (pintype "passive"))
      (node (ref "C5") (pin "1") (pinfunction "1_1") (pintype "passive"))
      (node (ref "C6") (pin "1") (pinfunction "1_1") (pintype "passive"))
      (node (ref "C7") (pin "1") (pinfunction "1_1") (pintype "passive"))
      (node (ref "D6") (pin "2") (pinfunction "A_2") (pintype "passive"))
      (node (ref "P2") (pin "2") (pinfunction "2_2") (pintype "passive"))
      (node (ref "R10") (pin "1") (pinfunction "1_1") (pintype "passive"))
      (node (ref "R18") (pin "2") (pinfunction "2_2") (pintype "passive"))
      (node (ref "R30") (pin "1") (pinfunction "1_1") (pintype "passive"))
      (node (ref "R6") (pin "2") (pinfunction "2_2") (pintype "passive"))
      (node (ref "R8") (pin "2") (pinfunction "2_2") (pintype "passive"))
      (node (ref "R9") (pin "1") (pinfunction "1_1") (pintype "passive"))
      (node (ref "TP6") (pin "1") (pintype "passive"))
      (node (ref "U10") (pin "5") (pinfunction "A2_5") (pintype "input"))
      (node (ref "U10") (pin "6") (pinfunction "A1_6") (pintype "input"))
      (node (ref "U10") (pin "7") (pinfunction "A0_7") (pintype "input"))
      (node (ref "U10") (pin "8") (pinfunction "VDD_8") (pintype "power_in"))
      (node (ref "U11") (pin "10") (pinfunction "~{MR}_10") (pintype "input"))
      (node (ref "U11") (pin "16") (pinfunction "VCC_16") (pintype "power_in"))
      (node (ref "U12") (pin "10") (pinfunction "VCC_10") (pintype "passive"))
      (node (ref "U12") (pin "12") (pinfunction "LEDA_12") (pintype "passive"))
      (node (ref "U2") (pin "1") (pinfunction "VDD_1") (pintype "power_in"))
      (node (ref "U2") (pin "17") (pinfunction "VDD_17") (pintype "power_in"))
      (node (ref "U2") (pin "5") (pinfunction "VDDA/VREF+_5") (pintype "power_in"))
      (node (ref "U3") (pin "5") (pinfunction "VOUT_5") (pintype "passive"))
      (node (ref "U5") (pin "10") (pinfunction "VDD_IO_10") (pintype "power_in"))
      (node (ref "U5") (pin "2") (pinfunction "CS_2") (pintype "passive"))
      (node (ref "U5") (pin "9") (pinfunction "VDD_9") (pintype "power_in"))
      (node (ref "U6") (pin "10") (pinfunction "VLED+_10") (pintype "output"))
      (node (ref "U6") (pin "9") (pinfunction "VLED+_9") (pintype "output"))
      (node (ref "U7") (pin "1") (pinfunction "IN_1") (pintype "power_in"))
      (node (ref "U7") (pin "3") (pinfunction "EN_3") (pintype "input"))
      (node (ref "U8") (pin "8") (pinfunction "VCC_8") (pintype "power_in"))
      (node (ref "U9") (pin "7") (pinfunction "VDD_7") (pintype "power_in"))
    )
    (net (code "43") (name "GND") (class "Default")
      (node (ref "C1") (pin "1") (pinfunction "1_1") (pintype "passive"))
      (node (ref "C10") (pin "1") (pinfunction "1_1") (pintype "passive"))
      (node (ref "C11") (pin "1") (pinfunction "1_1") (pintype "passive"))
      (node (ref "C12") (pin "1") (pinfunction "1_1") (pintype "passive"))
      (node (ref "C13") (pin "2") (pinfunction "2_2") (pintype "passive"))
      (node (ref "C14") (pin "2") (pinfunction "2_2") (pintype "passive"))
      (node (ref "C15") (pin "2") (pinfunction "2_2") (pintype "passive"))
      (node (ref "C16") (pin "2") (pinfunction "2_2") (pintype "passive"))
      (node (ref "C17") (pin "2") (pinfunction "2_2") (pintype "passive"))
      (node (ref "C18") (pin "2") (pinfunction "2_2") (pintype "passive"))
      (node (ref "C19") (pin "2") (pinfunction "2_2") (pintype "passive"))
      (node (ref "C2") (pin "1") (pinfunction "1_1") (pintype "passive"))
      (node (ref "C20") (pin "1") (pinfunction "1_1") (pintype "passive"))
      (node (ref "C21") (pin "1") (pinfunction "1_1") (pintype "passive"))
      (node (ref "C22") (pin "2") (pinfunction "2_2") (pintype "passive"))
      (node (ref "C23") (pin "2") (pinfunction "2_2") (pintype "passive"))
      (node (ref "C24") (pin "2") (pinfunction "2_2") (pintype "passive"))
      (node (ref "C25") (pin "2") (pinfunction "2_2") (pintype "passive"))
      (node (ref "C3") (pin "2") (pinfunction "2_2") (pintype "passive"))
      (node (ref "C4") (pin "2") (pinfunction "2_2") (pintype "passive"))
      (node (ref "C5") (pin "2") (pinfunction "2_2") (pintype "passive"))
      (node (ref "C6") (pin "2") (pinfunction "2_2") (pintype "passive"))
      (node (ref "C7") (pin "2") (pinfunction "2_2") (pintype "passive"))
      (node (ref "C8") (pin "2") (pinfunction "2_2") (pintype "passive"))
      (node (ref "C9") (pin "2") (pinfunction "2_2") (pintype "passive"))
      (node (ref "D10") (pin "1") (pinfunction "C_1") (pintype "passive"))
      (node (ref "D7") (pin "1") (pinfunction "C_1") (pintype "passive"))
      (node (ref "D8") (pin "1") (pinfunction "C_1") (pintype "passive"))
      (node (ref "D9") (pin "1") (pinfunction "C_1") (pintype "passive"))
      (node (ref "J1") (pin "1") (pinfunction "MNT_1_1") (pintype "power_in"))
      (node (ref "J1") (pin "2") (pinfunction "MNT_2_2") (pintype "power_in"))
      (node (ref "J1") (pin "3") (pinfunction "MNT_3_3") (pintype "power_in"))
      (node (ref "J1") (pin "4") (pinfunction "MNT_4_4") (pintype "power_in"))
      (node (ref "J1") (pin "A1-B12") (pinfunction "GND_A1-B12") (pintype "power_in"))
      (node (ref "J1") (pin "B1-A12") (pinfunction "GND_B1-A12") (pintype "bidirectional"))
      (node (ref "J2") (pin "1") (pinfunction "1_1") (pintype "passive"))
      (node (ref "P1") (pin "4") (pinfunction "4_4") (pintype "passive"))
      (node (ref "P2") (pin "4") (pinfunction "4_4") (pintype "passive"))
      (node (ref "Q2") (pin "2") (pinfunction "S_2") (pintype "passive"))
      (node (ref "Q3") (pin "2") (pinfunction "E_2") (pintype "passive"))
      (node (ref "Q4") (pin "2") (pinfunction "S_2") (pintype "passive"))
      (node (ref "Q5") (pin "2") (pinfunction "S_2") (pintype "passive"))
      (node (ref "R1") (pin "1") (pinfunction "1_1") (pintype "passive"))
      (node (ref "R11") (pin "1") (pinfunction "1_1") (pintype "passive"))
      (node (ref "R12") (pin "1") (pinfunction "1_1") (pintype "passive"))
      (node (ref "R13") (pin "1") (pinfunction "1_1") (pintype "passive"))
      (node (ref "R16") (pin "1") (pinfunction "1_1") (pintype "passive"))
      (node (ref "R19") (pin "1") (pinfunction "1_1") (pintype "passive"))
      (node (ref "R2") (pin "2") (pinfunction "2_2") (pintype "passive"))
      (node (ref "R20") (pin "1") (pinfunction "1_1") (pintype "passive"))
      (node (ref "R21") (pin "1") (pinfunction "1_1") (pintype "passive"))
      (node (ref "R27") (pin "1") (pinfunction "1_1") (pintype "passive"))
      (node (ref "R3") (pin "2") (pinfunction "2_2") (pintype "passive"))
      (node (ref "R31") (pin "2") (pinfunction "2_2") (pintype "passive"))
      (node (ref "R32") (pin "1") (pinfunction "1_1") (pintype "passive"))
      (node (ref "R33") (pin "1") (pinfunction "1_1") (pintype "passive"))
      (node (ref "R5") (pin "1") (pinfunction "1_1") (pintype "passive"))
      (node (ref "S1") (pin "4") (pinfunction "4_4") (pintype "passive"))
      (node (ref "S2") (pin "4") (pinfunction "4_4") (pintype "passive"))
      (node (ref "S3") (pin "1") (pinfunction "1_1") (pintype "passive"))
      (node (ref "SW1") (pin "1") (pinfunction "1_1") (pintype "passive"))
      (node (ref "TP1") (pin "1") (pintype "passive"))
      (node (ref "TP2") (pin "1") (pintype "passive"))
      (node (ref "U1") (pin "2") (pinfunction "VSS_2") (pintype "power_in"))
      (node (ref "U10") (pin "4") (pinfunction "GND_4") (pintype "power_in"))
      (node (ref "U10") (pin "9") (pinfunction "EP_9") (pintype "power_in"))
      (node (ref "U11") (pin "8") (pinfunction "GND_8") (pintype "power_in"))
      (node (ref "U12") (pin "13") (pinfunction "GND_13") (pintype "passive"))
      (node (ref "U12") (pin "8") (pinfunction "GND_8") (pintype "passive"))
      (node (ref "U2") (pin "16") (pinfunction "VSS_16") (pintype "power_in"))
      (node (ref "U2") (pin "32") (pinfunction "VSS_32") (pintype "power_in"))
      (node (ref "U2") (pin "33") (pinfunction "EP_33") (pintype "power_in"))
      (node (ref "U3") (pin "2") (pinfunction "VSS_2") (pintype "passive"))
      (node (ref "U4") (pin "13") (pinfunction "EP_13") (pintype "power_in"))
      (node (ref "U4") (pin "3") (pinfunction "VSS_3") (pintype "power_in"))
      (node (ref "U5") (pin "3") (pinfunction "SDO/SA0_3") (pintype "passive"))
      (node (ref "U5") (pin "6") (pinfunction "GND_6") (pintype "power_in"))
      (node (ref "U5") (pin "7") (pinfunction "RES_7") (pintype "passive"))
      (node (ref "U5") (pin "8") (pinfunction "GND_8") (pintype "power_in"))
      (node (ref "U6") (pin "12") (pinfunction "GND_12") (pintype "power_in"))
      (node (ref "U6") (pin "4") (pinfunction "PGND_4") (pintype "power_in"))
      (node (ref "U7") (pin "2") (pinfunction "GND_2") (pintype "power_in"))
      (node (ref "U8") (pin "1") (pinfunction "A0_1") (pintype "input"))
      (node (ref "U8") (pin "2") (pinfunction "A1_2") (pintype "input"))
      (node (ref "U8") (pin "3") (pinfunction "A2_3") (pintype "input"))
      (node (ref "U8") (pin "4") (pinfunction "VSS_4") (pintype "power_in"))
      (node (ref "U9") (pin "5") (pinfunction "VSS_5") (pintype "power_in"))
    )
    (net (code "44") (name "LDO_IN") (class "Default")
      (node (ref "C10") (pin "2") (pinfunction "2_2") (pintype "passive"))
      (node (ref "D1") (pin "1") (pinfunction "C_1") (pintype "passive"))
      (node (ref "Q1") (pin "2") (pinfunction "S_2") (pintype "passive"))
      (node (ref "U3") (pin "1") (pinfunction "VIN_1") (pintype "passive"))
    )
    (net (code "45") (name "Net-(D2-C)") (class "Default")
      (node (ref "D2") (pin "1") (pinfunction "C_1") (pintype "passive"))
      (node (ref "R4") (pin "1") (pinfunction "1_1") (pintype "passive"))
    )
    (net (code "46") (name "Net-(D4-C)") (class "Default")
      (node (ref "D4") (pin "1") (pinfunction "C_1") (pintype "passive"))
      (node (ref "R13") (pin "2") (pinfunction "2_2") (pintype "passive"))
    )
    (net (code "47") (name "Net-(D5-C)") (class "Default")
      (node (ref "D5") (pin "1") (pinfunction "C_1") (pintype "passive"))
      (node (ref "R14") (pin "2") (pinfunction "2_2") (pintype "passive"))
    )
    (net (code "48") (name "Net-(D6-C)") (class "Default")
      (node (ref "D6") (pin "1") (pinfunction "C_1") (pintype "passive"))
      (node (ref "R15") (pin "2") (pinfunction "2_2") (pintype "passive"))
    )
    (net (code "49") (name "Net-(D7-A)") (class "Default")
      (node (ref "D7") (pin "2") (pinfunction "A_2") (pintype "passive"))
      (node (ref "R22") (pin "1") (pinfunction "1_1") (pintype "passive"))
    )
    (net (code "50") (name "Net-(D8-A)") (class "Default")
      (node (ref "D8") (pin "2") (pinfunction "A_2") (pintype "passive"))
      (node (ref "R23") (pin "1") (pinfunction "1_1") (pintype "passive"))
    )
    (net (code "51") (name "Net-(D9-A)") (class "Default")
      (node (ref "D9") (pin "2") (pinfunction "A_2") (pintype "passive"))
      (node (ref "R24") (pin "1") (pinfunction "1_1") (pintype "passive"))
    )
    (net (code "52") (name "Net-(D10-A)") (class "Default")
      (node (ref "D10") (pin "2") (pinfunction "A_2") (pintype "passive"))
      (node (ref "R25") (pin "1") (pinfunction "1_1") (pintype "passive"))
    )
    (net (code "53") (name "Net-(D11-C)") (class "Default")
      (node (ref "D11") (pin "1") (pinfunction "C_1") (pintype "passive"))
      (node (ref "Q4") (pin "1") (pinfunction "G_1") (pintype "passive"))
      (node (ref "R32") (pin "2") (pinfunction "2_2") (pintype "passive"))
    )
    (net (code "54") (name "Net-(D12-C)") (class "Default")
      (node (ref "D12") (pin "1") (pinfunction "C_1") (pintype "passive"))
      (node (ref "Q5") (pin "1") (pinfunction "G_1") (pintype "passive"))
      (node (ref "R33") (pin "2") (pinfunction "2_2") (pintype "passive"))
    )
    (net (code "55") (name "Net-(J1-CC1)") (class "Default")
      (node (ref "J1") (pin "A5") (pinfunction "CC1_A5") (pintype "power_in"))
      (node (ref "R1") (pin "2") (pinfunction "2_2") (pintype "passive"))
    )
    (net (code "56") (name "Net-(J1-CC2)") (class "Default")
      (node (ref "J1") (pin "B5") (pinfunction "CC2_B5") (pintype "bidirectional"))
      (node (ref "R5") (pin "2") (pinfunction "2_2") (pintype "passive"))
    )
    (net (code "57") (name "Net-(Q1-D)") (class "Default")
      (node (ref "Q1") (pin "3") (pinfunction "D_3") (pintype "passive"))
      (node (ref "SW2") (pin "L1") (pinfunction "L1_L1") (pintype "passive"))
    )
    (net (code "58") (name "Net-(Q2-D)") (class "Default")
      (node (ref "Q2") (pin "3") (pinfunction "D_3") (pintype "passive"))
      (node (ref "R14") (pin "1") (pinfunction "1_1") (pintype "passive"))
      (node (ref "R15") (pin "1") (pinfunction "1_1") (pintype "passive"))
    )
    (net (code "59") (name "Net-(U6-~{INT})") (class "Default")
      (node (ref "R17") (pin "1") (pinfunction "1_1") (pintype "passive"))
      (node (ref "U6") (pin "13") (pinfunction "~{INT}_13") (pintype "input"))
    )
    (net (code "60") (name "Net-(U8-WP)") (class "Default")
      (node (ref "R19") (pin "2") (pinfunction "2_2") (pintype "passive"))
      (node (ref "U8") (pin "7") (pinfunction "WP_7") (pintype "input"))
    )
    (net (code "61") (name "Net-(U11-Q0)") (class "Default")
      (node (ref "R22") (pin "2") (pinfunction "2_2") (pintype "passive"))
      (node (ref "U11") (pin "15") (pinfunction "Q0_15") (pintype "output"))
    )
    (net (code "62") (name "Net-(U11-Q1)") (class "Default")
      (node (ref "R23") (pin "2") (pinfunction "2_2") (pintype "passive"))
      (node (ref "U11") (pin "1") (pinfunction "Q1_1") (pintype "output"))
    )
    (net (code "63") (name "Net-(U11-Q2)") (class "Default")
      (node (ref "R24") (pin "2") (pinfunction "2_2") (pintype "passive"))
      (node (ref "U11") (pin "2") (pinfunction "Q2_2") (pintype "output"))
    )
    (net (code "64") (name "Net-(U11-Q3)") (class "Default")
      (node (ref "R25") (pin "2") (pinfunction "2_2") (pintype "passive"))
      (node (ref "U11") (pin "3") (pinfunction "Q3_3") (pintype "output"))
    )
    (net (code "65") (name "PACK+") (class "Default")
      (node (ref "C8") (pin "1") (pinfunction "1_1") (pintype "passive"))
      (node (ref "J2") (pin "2") (pinfunction "2_2") (pintype "passive"))
      (node (ref "R7") (pin "2") (pinfunction "2_2") (pintype "passive"))
      (node (ref "U4") (pin "6") (pinfunction "BAT_6") (pintype "input"))
      (node (ref "U4") (pin "8") (pinfunction "SRP_8") (pintype "input"))
    )
    (net (code "66") (name "USB_VCC") (class "Default")
      (node (ref "C1") (pin "2") (pinfunction "2_2") (pintype "passive"))
      (node (ref "D1") (pin "2") (pinfunction "A_2") (pintype "passive"))
      (node (ref "D11") (pin "2") (pinfunction "A_2") (pintype "passive"))
      (node (ref "D2") (pin "2") (pinfunction "A_2") (pintype "passive"))
      (node (ref "D3") (pin "2") (pinfunction "A_2") (pintype "passive"))
      (node (ref "D4") (pin "2") (pinfunction "A_2") (pintype "passive"))
      (node (ref "J1") (pin "A4-B9") (pinfunction "VBUS_A4-B9") (pintype "power_in"))
      (node (ref "J1") (pin "B4-A9") (pinfunction "VBUS_B4-A9") (pintype "bidirectional"))
      (node (ref "TP3") (pin "1") (pintype "passive"))
      (node (ref "U1") (pin "4") (pinfunction "VDD_4") (pintype "power_in"))
    )
    (net (code "67") (name "VDD") (class "Default")
      (node (ref "C9") (pin "1") (pinfunction "1_1") (pintype "passive"))
      (node (ref "U4") (pin "5") (pinfunction "VDD_5") (pintype "power_in"))
    )
    (net (code "68") (name "VSYS") (class "Default")
      (node (ref "C2") (pin "2") (pinfunction "2_2") (pintype "passive"))
      (node (ref "R7") (pin "1") (pinfunction "1_1") (pintype "passive"))
      (node (ref "SW2") (pin "COM") (pinfunction "COM_COM") (pintype "passive"))
      (node (ref "U1") (pin "3") (pinfunction "VBAT_3") (pintype "power_in"))
      (node (ref "U4") (pin "7") (pinfunction "SRN_7") (pintype "input"))
    )
    (net (code "69") (name "unconnected-(J1-Dn1-PadA7)") (class "Default")
      (node (ref "J1") (pin "A7") (pinfunction "Dn1_A7") (pintype "bidirectional+no_connect"))
    )
    (net (code "70") (name "unconnected-(J1-Dn2-PadB7)") (class "Default")
      (node (ref "J1") (pin "B7") (pinfunction "Dn2_B7") (pintype "bidirectional+no_connect"))
    )
    (net (code "71") (name "unconnected-(J1-Dp1-PadA6)") (class "Default")
      (node (ref "J1") (pin "A6") (pinfunction "Dp1_A6") (pintype "bidirectional+no_connect"))
    )
    (net (code "72") (name "unconnected-(J1-Dp2-PadB6)") (class "Default")
      (node (ref "J1") (pin "B6") (pinfunction "Dp2_B6") (pintype "bidirectional+no_connect"))
    )
    (net (code "73") (name "unconnected-(J1-SBU1-PadA8)") (class "Default")
      (node (ref "J1") (pin "A8") (pinfunction "SBU1_A8") (pintype "bidirectional+no_connect"))
    )
    (net (code "74") (name "unconnected-(J1-SBU2-PadB8)") (class "Default")
      (node (ref "J1") (pin "B8") (pinfunction "SBU2_B8") (pintype "power_in+no_connect"))
    )
    (net (code "75") (name "unconnected-(S1-Pad2)") (class "Default")
      (node (ref "S1") (pin "2") (pinfunction "2_2") (pintype "passive+no_connect"))
    )
    (net (code "76") (name "unconnected-(S1-Pad3)") (class "Default")
      (node (ref "S1") (pin "3") (pinfunction "3_3") (pintype "passive+no_connect"))
    )
    (net (code "77") (name "unconnected-(S2-Pad2)") (class "Default")
      (node (ref "S2") (pin "2") (pinfunction "2_2") (pintype "passive+no_connect"))
    )
    (net (code "78") (name "unconnected-(S2-Pad3)") (class "Default")
      (node (ref "S2") (pin "3") (pinfunction "3_3") (pintype "passive+no_connect"))
    )
    (net (code "79") (name "unconnected-(SW2-PadL2)") (class "Default")
      (node (ref "SW2") (pin "L2") (pinfunction "L2_L2") (pintype "passive+no_connect"))
    )
    (net (code "80") (name "unconnected-(U3-NC-Pad3)") (class "Default")
      (node (ref "U3") (pin "3") (pinfunction "NC_3") (pintype "passive+no_connect"))
    )
    (net (code "81") (name "unconnected-(U3-NC-Pad4)") (class "Default")
      (node (ref "U3") (pin "4") (pinfunction "NC_4") (pintype "passive+no_connect"))
    )
    (net (code "82") (name "unconnected-(U4-NC-Pad4)") (class "Default")
      (node (ref "U4") (pin "4") (pinfunction "NC_4") (pintype "passive+no_connect"))
    )
    (net (code "83") (name "unconnected-(U4-NC-Pad9)") (class "Default")
      (node (ref "U4") (pin "9") (pinfunction "NC_9") (pintype "passive+no_connect"))
    )
    (net (code "84") (name "unconnected-(U4-NC-Pad11)") (class "Default")
      (node (ref "U4") (pin "11") (pinfunction "NC_11") (pintype "passive+no_connect"))
    )
    (net (code "85") (name "unconnected-(U5-INT1-Pad12)") (class "Default")
      (node (ref "U5") (pin "12") (pinfunction "INT1_12") (pintype "input+no_connect"))
    )
    (net (code "86") (name "unconnected-(U5-INT2-Pad11)") (class "Default")
      (node (ref "U5") (pin "11") (pinfunction "INT2_11") (pintype "input+no_connect"))
    )
    (net (code "87") (name "unconnected-(U5-NC-Pad5)") (class "Default")
      (node (ref "U5") (pin "5") (pinfunction "NC_5") (pintype "passive+no_connect"))
    )
    (net (code "88") (name "unconnected-(U6-NC-Pad1)") (class "Default")
      (node (ref "U6") (pin "1") (pinfunction "NC_1") (pintype "passive+no_connect"))
    )
    (net (code "89") (name "unconnected-(U6-NC-Pad5)") (class "Default")
      (node (ref "U6") (pin "5") (pinfunction "NC_5") (pintype "passive+no_connect"))
    )
    (net (code "90") (name "unconnected-(U6-NC-Pad6)") (class "Default")
      (node (ref "U6") (pin "6") (pinfunction "NC_6") (pintype "passive+no_connect"))
    )
    (net (code "91") (name "unconnected-(U6-NC-Pad7)") (class "Default")
      (node (ref "U6") (pin "7") (pinfunction "NC_7") (pintype "passive+no_connect"))
    )
    (net (code "92") (name "unconnected-(U6-NC-Pad8)") (class "Default")
      (node (ref "U6") (pin "8") (pinfunction "NC_8") (pintype "passive+no_connect"))
    )
    (net (code "93") (name "unconnected-(U6-NC-Pad14)") (class "Default")
      (node (ref "U6") (pin "14") (pinfunction "NC_14") (pintype "passive+no_connect"))
    )
    (net (code "94") (name "unconnected-(U7-NC-Pad4)") (class "Default")
      (node (ref "U7") (pin "4") (pinfunction "NC_4") (pintype "passive+no_connect"))
    )
    (net (code "95") (name "unconnected-(U9-CLKOUT-Pad1)") (class "Default")
      (node (ref "U9") (pin "1") (pinfunction "CLKOUT_1") (pintype "output+no_connect"))
    )
    (net (code "96") (name "unconnected-(U9-~{INT}-Pad2)") (class "Default")
      (node (ref "U9") (pin "2") (pinfunction "~{INT}_2") (pintype "input+no_connect"))
    )
    (net (code "97") (name "unconnected-(U11-Q4-Pad4)") (class "Default")
      (node (ref "U11") (pin "4") (pinfunction "Q4_4") (pintype "output+no_connect"))
    )
    (net (code "98") (name "unconnected-(U11-Q5-Pad5)") (class "Default")
      (node (ref "U11") (pin "5") (pinfunction "Q5_5") (pintype "output+no_connect"))
    )
    (net (code "99") (name "unconnected-(U11-Q6-Pad6)") (class "Default")
      (node (ref "U11") (pin "6") (pinfunction "Q6_6") (pintype "output+no_connect"))
    )
    (net (code "100") (name "unconnected-(U11-Q7-Pad7)") (class "Default")
      (node (ref "U11") (pin "7") (pinfunction "Q7_7") (pintype "output+no_connect"))
    )
    (net (code "101") (name "unconnected-(U11-Q7S-Pad9)") (class "Default")
      (node (ref "U11") (pin "9") (pinfunction "Q7S_9") (pintype "output+no_connect"))
    )
    (net (code "102") (name "unconnected-(U12-NC-Pad9)") (class "Default")
      (node (ref "U12") (pin "9") (pinfunction "NC_9") (pintype "passive+no_connect"))
    )
  )
)
